# car-radar.net
KiCad netlist of a schematic drawn in Altium Designer
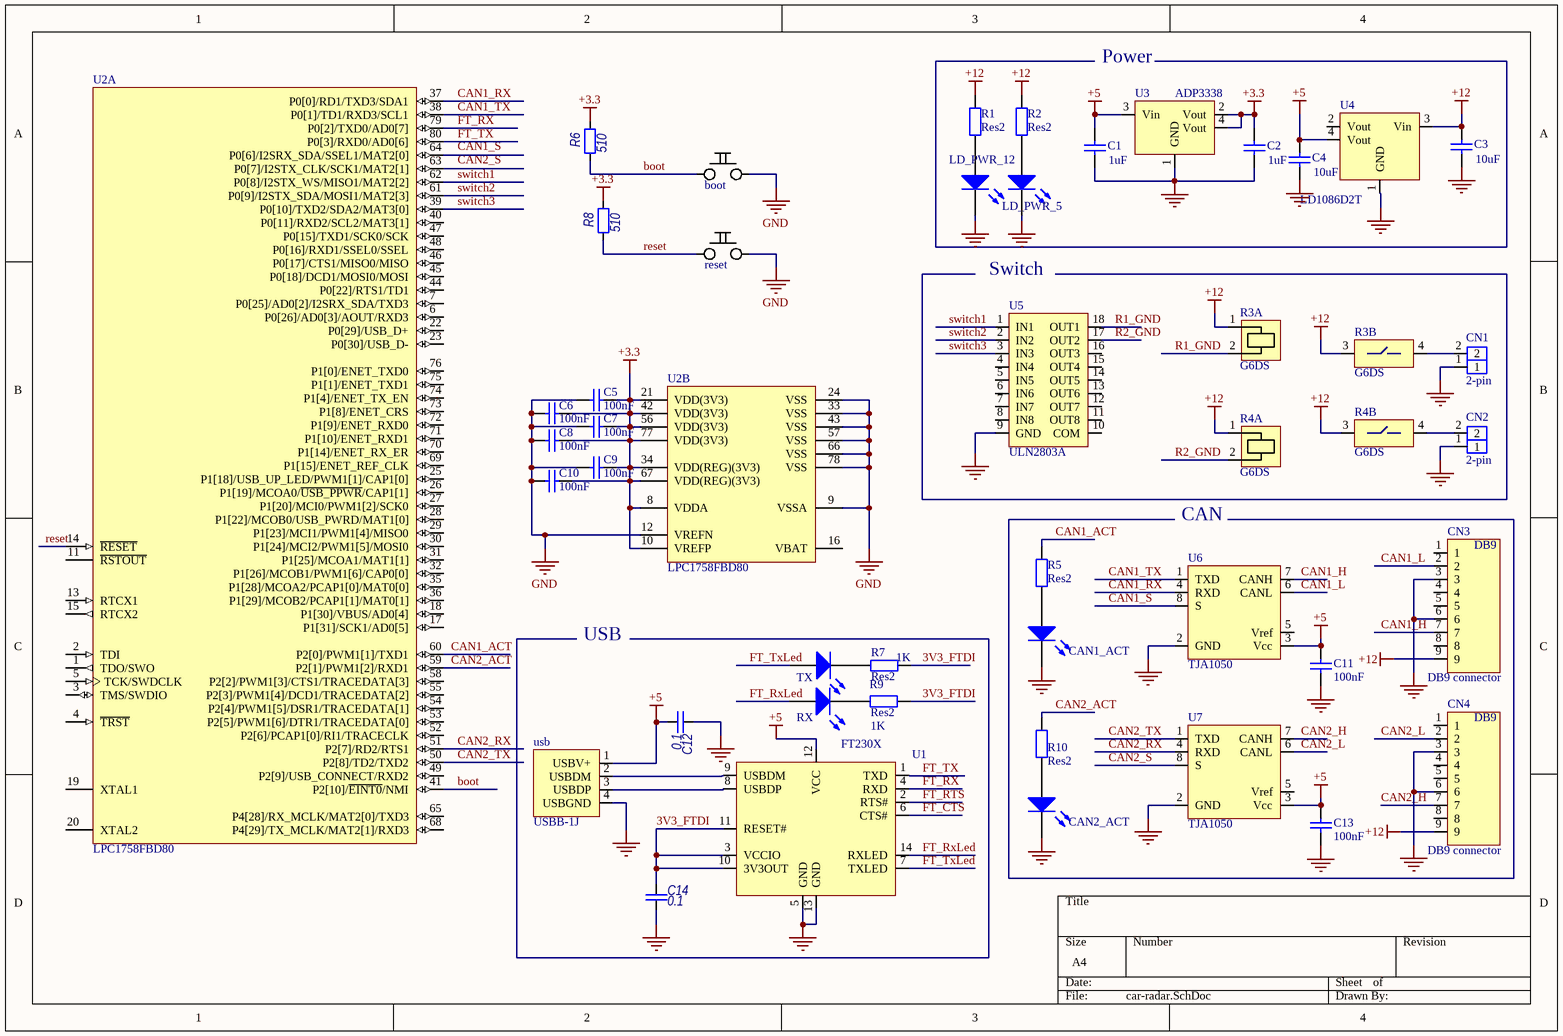
[diagram p0: car-radar.SchDoc]

(export (version "E")
  (design (tool "Eeschema 10.0.6"))
  (components
    (comp (ref "boot")
      (value "chip button")
      (footprint "BUTTON SMD")
      (libsource (lib "Schlib1") (part "chip button"))
    )
    (comp (ref "C1")
      (value "1uF")
      (footprint "CAPC1608M")
      (description "Capacitor")
      (fields (field (name "Comment") "Cap") (field (name "PUBLISHER") "Altium Limited"))
      (libsource (lib "Miscellaneous Devices") (part "Cap"))
    )
    (comp (ref "C2")
      (value "1uF")
      (footprint "CAPC1608M")
      (description "Capacitor")
      (fields (field (name "Comment") "Cap") (field (name "PUBLISHER") "Altium Limited"))
      (libsource (lib "Miscellaneous Devices") (part "Cap"))
    )
    (comp (ref "C3")
      (value "10uF")
      (footprint "CAPC1608N")
      (description "Capacitor")
      (fields (field (name "Comment") "Cap") (field (name "PUBLISHER") "Altium Limited"))
      (libsource (lib "Miscellaneous Devices") (part "Cap"))
    )
    (comp (ref "C4")
      (value "10uF")
      (footprint "CAPC1608N")
      (description "Capacitor")
      (fields (field (name "Comment") "Cap") (field (name "PUBLISHER") "Altium Limited"))
      (libsource (lib "Miscellaneous Devices") (part "Cap"))
    )
    (comp (ref "C5")
      (value "100nF")
      (footprint "CAPC1608N")
      (description "Capacitor")
      (fields (field (name "Comment") "p") (field (name "PUBLISHER") "Altium Limited"))
      (libsource (lib "Miscellaneous Devices") (part "Cap"))
    )
    (comp (ref "C6")
      (value "100nF")
      (footprint "CAPC1608N")
      (description "Capacitor")
      (fields (field (name "Comment") "p") (field (name "PUBLISHER") "Altium Limited"))
      (libsource (lib "Miscellaneous Devices") (part "Cap"))
    )
    (comp (ref "C7")
      (value "100nF")
      (footprint "CAPC1608N")
      (description "Capacitor")
      (fields (field (name "Comment") "p") (field (name "PUBLISHER") "Altium Limited"))
      (libsource (lib "Miscellaneous Devices") (part "Cap"))
    )
    (comp (ref "C8")
      (value "100nF")
      (footprint "CAPC1608N")
      (description "Capacitor")
      (fields (field (name "Comment") "p") (field (name "PUBLISHER") "Altium Limited"))
      (libsource (lib "Miscellaneous Devices") (part "Cap"))
    )
    (comp (ref "C9")
      (value "100nF")
      (footprint "CAPC1608N")
      (description "Capacitor")
      (fields (field (name "Comment") "p") (field (name "PUBLISHER") "Altium Limited"))
      (libsource (lib "Miscellaneous Devices") (part "Cap"))
    )
    (comp (ref "C10")
      (value "100nF")
      (footprint "CAPC1608N")
      (description "Capacitor")
      (fields (field (name "Comment") "p") (field (name "PUBLISHER") "Altium Limited"))
      (libsource (lib "Miscellaneous Devices") (part "Cap"))
    )
    (comp (ref "C11")
      (value "100nF")
      (footprint "CAPC1608N")
      (description "Capacitor")
      (fields (field (name "Comment") "p") (field (name "PUBLISHER") "Altium Limited"))
      (libsource (lib "Miscellaneous Devices") (part "Cap"))
    )
    (comp (ref "C12")
      (value "0.1")
      (footprint "CAPC1608M")
      (description "Ceramic capacitors")
      (libsource (lib "RCL") (part "Cap"))
    )
    (comp (ref "C13")
      (value "100nF")
      (footprint "CAPC1608N")
      (description "Capacitor")
      (fields (field (name "Comment") "p") (field (name "PUBLISHER") "Altium Limited"))
      (libsource (lib "Miscellaneous Devices") (part "Cap"))
    )
    (comp (ref "C14")
      (value "0.1")
      (footprint "Cap_0805")
      (description "Ceramic capacitors")
      (libsource (lib "RCL") (part "Cap"))
    )
    (comp (ref "CAN1_ACT")
      (value "led")
      (footprint "RESC1608M")
      (description "chip led")
      (libsource (lib "Schlib1") (part "chip led"))
    )
    (comp (ref "CAN2_ACT")
      (value "led")
      (footprint "RESC1608M")
      (description "chip led")
      (libsource (lib "Schlib1") (part "chip led"))
    )
    (comp (ref "CN1") (value "2-pin") (libsource (lib "Con sch") (part "2-pin")))
    (comp (ref "CN2") (value "2-pin") (libsource (lib "Con sch") (part "2-pin")))
    (comp (ref "CN3")
      (value "DB9 connector")
      (footprint "Con Rect Stag PCB:DSUB1.385-2H9C")
      (libsource (lib "Schlib1") (part "DB9 разъём"))
    )
    (comp (ref "CN4")
      (value "DB9 connector")
      (footprint "Con Rect Stag PCB:DSUB1.385-2H9C")
      (libsource (lib "Schlib1") (part "DB9 разъём"))
    )
    (comp (ref "LD_PWR_5")
      (value "led")
      (footprint "RESC1608M")
      (description "chip led")
      (libsource (lib "Schlib1") (part "chip led"))
    )
    (comp (ref "LD_PWR_12")
      (value "led")
      (footprint "RESC1608M")
      (description "chip led")
      (libsource (lib "Schlib1") (part "chip led"))
    )
    (comp (ref "R1")
      (value "Res2")
      (footprint "RESC3216M")
      (description "Resistor")
      (fields (field (name "PUBLISHER") "Altium Limited"))
      (libsource (lib "Miscellaneous Devices") (part "Res2"))
    )
    (comp (ref "R2")
      (value "Res2")
      (footprint "RESC3216M")
      (description "Resistor")
      (fields (field (name "PUBLISHER") "Altium Limited"))
      (libsource (lib "Miscellaneous Devices") (part "Res2"))
    )
    (comp (ref "R3")
      (value "G6DS")
      (description "SPST-NO rele")
      (libsource (lib "Schlib1") (part "rele-SPST-NO"))
    )
    (comp (ref "R4")
      (value "G6DS")
      (description "SPST-NO rele")
      (libsource (lib "Schlib1") (part "rele-SPST-NO"))
    )
    (comp (ref "R5")
      (value "Res2")
      (footprint "RESC3216M")
      (description "Resistor")
      (fields (field (name "PUBLISHER") "Altium Limited"))
      (libsource (lib "Miscellaneous Devices") (part "Res2"))
    )
    (comp (ref "R6")
      (value "510")
      (footprint "RESC2012M")
      (description "Ceramic resisors")
      (libsource (lib "RCL") (part "Res"))
    )
    (comp (ref "R7")
      (value "Res2")
      (footprint "RESC3216M")
      (description "Resistor")
      (fields (field (name "ALTIUM_VALUE") "1K") (field (name "PUBLISHER") "Altium Limited"))
      (libsource (lib "") (part "Res2_1"))
    )
    (comp (ref "R8")
      (value "510")
      (footprint "RESC2012M")
      (description "Ceramic resisors")
      (libsource (lib "RCL") (part "Res"))
    )
    (comp (ref "R9")
      (value "Res2")
      (footprint "RESC3216M")
      (description "Resistor")
      (fields (field (name "ALTIUM_VALUE") "1K") (field (name "PUBLISHER") "Altium Limited"))
      (libsource (lib "") (part "Res2_1"))
    )
    (comp (ref "R10")
      (value "Res2")
      (footprint "RESC3216M")
      (description "Resistor")
      (fields (field (name "PUBLISHER") "Altium Limited"))
      (libsource (lib "Miscellaneous Devices") (part "Res2"))
    )
    (comp (ref "reset")
      (value "chip button")
      (footprint "BUTTON SMD")
      (libsource (lib "Schlib1") (part "chip button"))
    )
    (comp (ref "RX")
      (value "led")
      (footprint "RESC2012M")
      (description "chip led")
      (libsource (lib "Schlib1") (part "chip led"))
    )
    (comp (ref "TX")
      (value "led")
      (footprint "RESC2012M")
      (description "chip led")
      (libsource (lib "Schlib1") (part "chip led"))
    )
    (comp (ref "U1")
      (value "FT230X")
      (footprint "SOP635P600-16N")
      (libsource (lib "Schlib1") (part "FT230X"))
    )
    (comp (ref "U2")
      (value "LPC1758FBD80")
      (footprint "SOT315-1_V")
      (libsource (lib "") (part "LPC1758FBD80_1"))
    )
    (comp (ref "U3")
      (value "ADP3338")
      (footprint "SOT223-4M")
      (description "ADP3339AKCZ-3.3-R7")
      (libsource (lib "Schlib1") (part "ADP3339"))
    )
    (comp (ref "U4")
      (value "LD1086D2T")
      (footprint "TO228P960-3_4M")
      (description "st LD1086D2T")
      (libsource (lib "Schlib1") (part "LD1086D2T"))
    )
    (comp (ref "U5")
      (value "ULN2803A")
      (footprint "SOIC127P1030-18L")
      (description "EIGHT DARLINGTON ARRAYS")
      (libsource (lib "Schlib1") (part "ULN2803A"))
    )
    (comp (ref "U6")
      (value "TJA1050")
      (description "High speed CAN transceiver")
      (libsource (lib "nxp") (part "TJA1050"))
    )
    (comp (ref "U7")
      (value "TJA1050")
      (description "High speed CAN transceiver")
      (libsource (lib "nxp") (part "TJA1050"))
    )
    (comp (ref "usb") (value "USBB-1J") (footprint "USB2.5-2V4") (libsource (lib "Schlib1") (part "USBB-1J")))
  )
  (nets
    (net (code "1") (name "+3.3") (class "Default")
      (node (ref "C10") (pin "2") (pinfunction "2_2") (pintype "passive"))
      (node (ref "C2") (pin "1") (pinfunction "1_1") (pintype "passive"))
      (node (ref "C5") (pin "2") (pinfunction "2_2") (pintype "passive"))
      (node (ref "C6") (pin "2") (pinfunction "2_2") (pintype "passive"))
      (node (ref "C7") (pin "2") (pinfunction "2_2") (pintype "passive"))
      (node (ref "C8") (pin "2") (pinfunction "2_2") (pintype "passive"))
      (node (ref "C9") (pin "2") (pinfunction "2_2") (pintype "passive"))
      (node (ref "R6") (pin "2") (pinfunction "2_2") (pintype "passive"))
      (node (ref "R8") (pin "2") (pinfunction "2_2") (pintype "passive"))
      (node (ref "U2") (pin "10") (pinfunction "VREFP_10") (pintype "power_in"))
      (node (ref "U2") (pin "21") (pinfunction "VDD(3V3)_21") (pintype "power_in"))
      (node (ref "U2") (pin "34") (pinfunction "VDD(REG)(3V3)_34") (pintype "power_in"))
      (node (ref "U2") (pin "42") (pinfunction "VDD(3V3)_42") (pintype "power_in"))
      (node (ref "U2") (pin "56") (pinfunction "VDD(3V3)_56") (pintype "power_in"))
      (node (ref "U2") (pin "67") (pinfunction "VDD(REG)(3V3)_67") (pintype "power_in"))
      (node (ref "U2") (pin "77") (pinfunction "VDD(3V3)_77") (pintype "power_in"))
      (node (ref "U2") (pin "8") (pinfunction "VDDA_8") (pintype "power_in"))
      (node (ref "U3") (pin "2") (pinfunction "Vout_2") (pintype "power_in"))
      (node (ref "U3") (pin "4") (pinfunction "Vout_4") (pintype "passive"))
    )
    (net (code "2") (name "+5") (class "Default")
      (node (ref "C1") (pin "1") (pinfunction "1_1") (pintype "passive"))
      (node (ref "C11") (pin "2") (pinfunction "2_2") (pintype "passive"))
      (node (ref "C12") (pin "2") (pinfunction "2_2") (pintype "passive"))
      (node (ref "C13") (pin "2") (pinfunction "2_2") (pintype "passive"))
      (node (ref "C4") (pin "1") (pinfunction "1_1") (pintype "passive"))
      (node (ref "U1") (pin "12") (pinfunction "VCC_12") (pintype "passive"))
      (node (ref "U3") (pin "3") (pinfunction "Vin_3") (pintype "power_in"))
      (node (ref "U4") (pin "4") (pinfunction "Vout_4") (pintype "passive"))
      (node (ref "U6") (pin "3") (pinfunction "Vcc_3") (pintype "passive"))
      (node (ref "U7") (pin "3") (pinfunction "Vcc_3") (pintype "passive"))
      (node (ref "usb") (pin "1") (pinfunction "USBV+_1") (pintype "power_in"))
    )
    (net (code "3") (name "+12") (class "Default")
      (node (ref "C3") (pin "1") (pinfunction "1_1") (pintype "passive"))
      (node (ref "CN3") (pin "9") (pinfunction "9_9") (pintype "passive"))
      (node (ref "CN4") (pin "9") (pinfunction "9_9") (pintype "passive"))
      (node (ref "R1") (pin "2") (pinfunction "2_2") (pintype "passive"))
      (node (ref "R2") (pin "2") (pinfunction "2_2") (pintype "passive"))
      (node (ref "R3") (pin "1") (pintype "passive"))
      (node (ref "R3") (pin "3") (pintype "passive"))
      (node (ref "R4") (pin "1") (pintype "passive"))
      (node (ref "R4") (pin "3") (pintype "passive"))
      (node (ref "U4") (pin "3") (pinfunction "Vin_3") (pintype "passive"))
    )
    (net (code "4") (name "/3V3_FTDI") (class "Default")
      (node (ref "C14") (pin "1") (pinfunction "1_1") (pintype "passive"))
      (node (ref "R7") (pin "1") (pinfunction "1_1") (pintype "passive"))
      (node (ref "R9") (pin "1") (pinfunction "1_1") (pintype "passive"))
      (node (ref "U1") (pin "10") (pinfunction "3V3OUT_10") (pintype "passive"))
      (node (ref "U1") (pin "11") (pinfunction "RESET#_11") (pintype "passive"))
      (node (ref "U1") (pin "3") (pinfunction "VCCIO_3") (pintype "passive"))
    )
    (net (code "5") (name "/CAN1_ACT") (class "Default")
      (node (ref "R5") (pin "2") (pinfunction "2_2") (pintype "passive"))
      (node (ref "U2") (pin "60") (pinfunction "P2[0]/PWM1[1]/TXD1_60") (pintype "bidirectional"))
    )
    (net (code "6") (name "/CAN1_H") (class "Default")
      (node (ref "CN3") (pin "7") (pinfunction "7_7") (pintype "passive"))
      (node (ref "U6") (pin "7") (pinfunction "CANH_7") (pintype "passive"))
    )
    (net (code "7") (name "/CAN1_L") (class "Default")
      (node (ref "CN3") (pin "2") (pinfunction "2_2") (pintype "passive"))
      (node (ref "U6") (pin "6") (pinfunction "CANL_6") (pintype "passive"))
    )
    (net (code "8") (name "/CAN1_RX") (class "Default")
      (node (ref "U2") (pin "37") (pinfunction "P0[0]/RD1/TXD3/SDA1_37") (pintype "bidirectional"))
      (node (ref "U6") (pin "4") (pinfunction "RXD_4") (pintype "passive"))
    )
    (net (code "9") (name "/CAN1_S") (class "Default")
      (node (ref "U6") (pin "8") (pinfunction "S_8") (pintype "passive"))
    )
    (net (code "10") (name "/CAN1_TX") (class "Default")
      (node (ref "U2") (pin "38") (pinfunction "P0[1]/TD1/RXD3/SCL1_38") (pintype "bidirectional"))
      (node (ref "U6") (pin "1") (pinfunction "TXD_1") (pintype "passive"))
    )
    (net (code "11") (name "/CAN2_ACT") (class "Default")
      (node (ref "R10") (pin "2") (pinfunction "2_2") (pintype "passive"))
      (node (ref "U2") (pin "59") (pinfunction "P2[1]/PWM1[2]/RXD1_59") (pintype "bidirectional"))
    )
    (net (code "12") (name "/CAN2_H") (class "Default")
      (node (ref "CN4") (pin "7") (pinfunction "7_7") (pintype "passive"))
      (node (ref "U7") (pin "7") (pinfunction "CANH_7") (pintype "passive"))
    )
    (net (code "13") (name "/CAN2_L") (class "Default")
      (node (ref "CN4") (pin "2") (pinfunction "2_2") (pintype "passive"))
      (node (ref "U7") (pin "6") (pinfunction "CANL_6") (pintype "passive"))
    )
    (net (code "14") (name "/CAN2_RX") (class "Default")
      (node (ref "U2") (pin "51") (pinfunction "P2[7]/RD2/RTS1_51") (pintype "bidirectional"))
      (node (ref "U7") (pin "4") (pinfunction "RXD_4") (pintype "passive"))
    )
    (net (code "15") (name "/CAN2_S") (class "Default")
      (node (ref "U7") (pin "8") (pinfunction "S_8") (pintype "passive"))
    )
    (net (code "16") (name "/CAN2_TX") (class "Default")
      (node (ref "U2") (pin "50") (pinfunction "P2[8]/TD2/TXD2_50") (pintype "bidirectional"))
      (node (ref "U7") (pin "1") (pinfunction "TXD_1") (pintype "passive"))
    )
    (net (code "17") (name "/FT_CTS") (class "Default")
      (node (ref "U1") (pin "6") (pinfunction "CTS#_6") (pintype "passive"))
    )
    (net (code "18") (name "/FT_RTS") (class "Default")
      (node (ref "U1") (pin "2") (pinfunction "RTS#_2") (pintype "passive"))
    )
    (net (code "19") (name "/FT_RX") (class "Default")
      (node (ref "U1") (pin "4") (pinfunction "RXD_4") (pintype "passive"))
      (node (ref "U2") (pin "79") (pinfunction "P0[2]/TXD0/AD0[7]_79") (pintype "bidirectional"))
    )
    (net (code "20") (name "/FT_RxLed") (class "Default")
      (node (ref "RX") (pin "1") (pinfunction "A_1") (pintype "passive"))
      (node (ref "U1") (pin "14") (pinfunction "RXLED_14") (pintype "passive"))
    )
    (net (code "21") (name "/FT_TX") (class "Default")
      (node (ref "U1") (pin "1") (pinfunction "TXD_1") (pintype "passive"))
      (node (ref "U2") (pin "80") (pinfunction "P0[3]/RXD0/AD0[6]_80") (pintype "bidirectional"))
    )
    (net (code "22") (name "/FT_TxLed") (class "Default")
      (node (ref "TX") (pin "1") (pinfunction "A_1") (pintype "passive"))
      (node (ref "U1") (pin "7") (pinfunction "TXLED_7") (pintype "passive"))
    )
    (net (code "23") (name "/R1_GND") (class "Default")
      (node (ref "R3") (pin "2") (pintype "passive"))
      (node (ref "U5") (pin "18") (pinfunction "OUT1_18") (pintype "passive"))
    )
    (net (code "24") (name "/R2_GND") (class "Default")
      (node (ref "R4") (pin "2") (pintype "passive"))
      (node (ref "U5") (pin "17") (pinfunction "OUT2_17") (pintype "passive"))
    )
    (net (code "25") (name "/boot") (class "Default")
      (node (ref "R6") (pin "1") (pinfunction "1_1") (pintype "passive"))
      (node (ref "U2") (pin "41") (pinfunction "P2[10]/~{EINT0}/NMI_41") (pintype "bidirectional"))
      (node (ref "boot") (pin "1") (pinfunction "1_1") (pintype "passive"))
    )
    (net (code "26") (name "/reset") (class "Default")
      (node (ref "R8") (pin "1") (pinfunction "1_1") (pintype "passive"))
      (node (ref "U2") (pin "14") (pinfunction "~{RESET}_14") (pintype "input"))
      (node (ref "reset") (pin "1") (pinfunction "1_1") (pintype "passive"))
    )
    (net (code "27") (name "/switch1") (class "Default")
      (node (ref "U2") (pin "62") (pinfunction "P0[8]/I2STX_WS/MISO1/MAT2[2]_62") (pintype "bidirectional"))
      (node (ref "U5") (pin "1") (pinfunction "IN1_1") (pintype "passive"))
    )
    (net (code "28") (name "/switch2") (class "Default")
      (node (ref "U2") (pin "61") (pinfunction "P0[9]/I2STX_SDA/MOSI1/MAT2[3]_61") (pintype "bidirectional"))
      (node (ref "U5") (pin "2") (pinfunction "IN2_2") (pintype "passive"))
    )
    (net (code "29") (name "/switch3") (class "Default")
      (node (ref "U2") (pin "39") (pinfunction "P0[10]/TXD2/SDA2/MAT3[0]_39") (pintype "bidirectional"))
      (node (ref "U5") (pin "3") (pinfunction "IN3_3") (pintype "passive"))
    )
    (net (code "30") (name "GND") (class "Default")
      (node (ref "C1") (pin "2") (pinfunction "2_2") (pintype "passive"))
      (node (ref "C10") (pin "1") (pinfunction "1_1") (pintype "passive"))
      (node (ref "C11") (pin "1") (pinfunction "1_1") (pintype "passive"))
      (node (ref "C12") (pin "1") (pinfunction "1_1") (pintype "passive"))
      (node (ref "C13") (pin "1") (pinfunction "1_1") (pintype "passive"))
      (node (ref "C14") (pin "2") (pinfunction "2_2") (pintype "passive"))
      (node (ref "C2") (pin "2") (pinfunction "2_2") (pintype "passive"))
      (node (ref "C3") (pin "2") (pinfunction "2_2") (pintype "passive"))
      (node (ref "C4") (pin "2") (pinfunction "2_2") (pintype "passive"))
      (node (ref "C5") (pin "1") (pinfunction "1_1") (pintype "passive"))
      (node (ref "C6") (pin "1") (pinfunction "1_1") (pintype "passive"))
      (node (ref "C7") (pin "1") (pinfunction "1_1") (pintype "passive"))
      (node (ref "C8") (pin "1") (pinfunction "1_1") (pintype "passive"))
      (node (ref "C9") (pin "1") (pinfunction "1_1") (pintype "passive"))
      (node (ref "CAN1_ACT") (pin "2") (pinfunction "K_2") (pintype "passive"))
      (node (ref "CAN2_ACT") (pin "2") (pinfunction "K_2") (pintype "passive"))
      (node (ref "CN1") (pin "1") (pinfunction "1_1") (pintype "passive"))
      (node (ref "CN2") (pin "1") (pinfunction "1_1") (pintype "passive"))
      (node (ref "CN3") (pin "3") (pinfunction "3_3") (pintype "passive"))
      (node (ref "CN3") (pin "6") (pinfunction "6_6") (pintype "passive"))
      (node (ref "CN4") (pin "3") (pinfunction "3_3") (pintype "passive"))
      (node (ref "CN4") (pin "6") (pinfunction "6_6") (pintype "passive"))
      (node (ref "LD_PWR_12") (pin "2") (pinfunction "K_2") (pintype "passive"))
      (node (ref "LD_PWR_5") (pin "2") (pinfunction "K_2") (pintype "passive"))
      (node (ref "U1") (pin "13") (pinfunction "GND_13") (pintype "passive"))
      (node (ref "U1") (pin "5") (pinfunction "GND_5") (pintype "passive"))
      (node (ref "U2") (pin "12") (pinfunction "VREFN_12") (pintype "power_in"))
      (node (ref "U2") (pin "24") (pinfunction "VSS_24") (pintype "power_in"))
      (node (ref "U2") (pin "33") (pinfunction "VSS_33") (pintype "power_in"))
      (node (ref "U2") (pin "43") (pinfunction "VSS_43") (pintype "power_in"))
      (node (ref "U2") (pin "57") (pinfunction "VSS_57") (pintype "power_in"))
      (node (ref "U2") (pin "66") (pinfunction "VSS_66") (pintype "power_in"))
      (node (ref "U2") (pin "78") (pinfunction "VSS_78") (pintype "power_in"))
      (node (ref "U2") (pin "9") (pinfunction "VSSA_9") (pintype "power_in"))
      (node (ref "U3") (pin "1") (pinfunction "GND_1") (pintype "power_in"))
      (node (ref "U4") (pin "1") (pinfunction "GND_1") (pintype "passive"))
      (node (ref "U5") (pin "9") (pinfunction "GND_9") (pintype "passive"))
      (node (ref "U6") (pin "2") (pinfunction "GND_2") (pintype "passive"))
      (node (ref "U7") (pin "2") (pinfunction "GND_2") (pintype "passive"))
      (node (ref "boot") (pin "2") (pinfunction "2_2") (pintype "passive"))
      (node (ref "reset") (pin "2") (pinfunction "2_2") (pintype "passive"))
      (node (ref "usb") (pin "4") (pinfunction "USBGND_4") (pintype "power_in"))
    )
    (net (code "31") (name "Net-(CAN1_ACT-A)") (class "Default")
      (node (ref "CAN1_ACT") (pin "1") (pinfunction "A_1") (pintype "passive"))
      (node (ref "R5") (pin "1") (pinfunction "1_1") (pintype "passive"))
    )
    (net (code "32") (name "Net-(CAN2_ACT-A)") (class "Default")
      (node (ref "CAN2_ACT") (pin "1") (pinfunction "A_1") (pintype "passive"))
      (node (ref "R10") (pin "1") (pinfunction "1_1") (pintype "passive"))
    )
    (net (code "33") (name "Net-(CN1-Pad2)") (class "Default")
      (node (ref "CN1") (pin "2") (pinfunction "2_2") (pintype "passive"))
      (node (ref "R3") (pin "4") (pintype "passive"))
    )
    (net (code "34") (name "Net-(CN2-Pad2)") (class "Default")
      (node (ref "CN2") (pin "2") (pinfunction "2_2") (pintype "passive"))
      (node (ref "R4") (pin "4") (pintype "passive"))
    )
    (net (code "35") (name "Net-(LD_PWR_5-A)") (class "Default")
      (node (ref "LD_PWR_5") (pin "1") (pinfunction "A_1") (pintype "passive"))
      (node (ref "R2") (pin "1") (pinfunction "1_1") (pintype "passive"))
    )
    (net (code "36") (name "Net-(LD_PWR_12-A)") (class "Default")
      (node (ref "LD_PWR_12") (pin "1") (pinfunction "A_1") (pintype "passive"))
      (node (ref "R1") (pin "1") (pinfunction "1_1") (pintype "passive"))
    )
    (net (code "37") (name "Net-(RX-K)") (class "Default")
      (node (ref "R9") (pin "2") (pinfunction "2_2") (pintype "passive"))
      (node (ref "RX") (pin "2") (pinfunction "K_2") (pintype "passive"))
    )
    (net (code "38") (name "Net-(TX-K)") (class "Default")
      (node (ref "R7") (pin "2") (pinfunction "2_2") (pintype "passive"))
      (node (ref "TX") (pin "2") (pinfunction "K_2") (pintype "passive"))
    )
    (net (code "39") (name "Net-(U1-USBDM)") (class "Default")
      (node (ref "U1") (pin "9") (pinfunction "USBDM_9") (pintype "passive"))
      (node (ref "usb") (pin "2") (pinfunction "USBDM_2") (pintype "passive"))
    )
    (net (code "40") (name "Net-(U1-USBDP)") (class "Default")
      (node (ref "U1") (pin "8") (pinfunction "USBDP_8") (pintype "passive"))
      (node (ref "usb") (pin "3") (pinfunction "USBDP_3") (pintype "passive"))
    )
    (net (code "41") (name "unconnected-(CN3-Pad1)") (class "Default")
      (node (ref "CN3") (pin "1") (pinfunction "1_1") (pintype "passive"))
    )
    (net (code "42") (name "unconnected-(CN3-Pad4)") (class "Default")
      (node (ref "CN3") (pin "4") (pinfunction "4_4") (pintype "passive"))
    )
    (net (code "43") (name "unconnected-(CN3-Pad5)") (class "Default")
      (node (ref "CN3") (pin "5") (pinfunction "5_5") (pintype "passive"))
    )
    (net (code "44") (name "unconnected-(CN3-Pad8)") (class "Default")
      (node (ref "CN3") (pin "8") (pinfunction "8_8") (pintype "passive"))
    )
    (net (code "45") (name "unconnected-(CN4-Pad1)") (class "Default")
      (node (ref "CN4") (pin "1") (pinfunction "1_1") (pintype "passive"))
    )
    (net (code "46") (name "unconnected-(CN4-Pad4)") (class "Default")
      (node (ref "CN4") (pin "4") (pinfunction "4_4") (pintype "passive"))
    )
    (net (code "47") (name "unconnected-(CN4-Pad5)") (class "Default")
      (node (ref "CN4") (pin "5") (pinfunction "5_5") (pintype "passive"))
    )
    (net (code "48") (name "unconnected-(CN4-Pad8)") (class "Default")
      (node (ref "CN4") (pin "8") (pinfunction "8_8") (pintype "passive"))
    )
    (net (code "49") (name "unconnected-(U1-CBUS0-Pad15)") (class "Default")
      (node (ref "U1") (pin "15") (pinfunction "CBUS0_15") (pintype "passive"))
    )
    (net (code "50") (name "unconnected-(U1-CBUS3-Pad16)") (class "Default")
      (node (ref "U1") (pin "16") (pinfunction "CBUS3_16") (pintype "passive"))
    )
    (net (code "51") (name "unconnected-(U2A-P0[6]{slash}I2SRX_SDA{slash}SSEL1{slash}MAT2[0]-Pad64)") (class "Default")
      (node (ref "U2") (pin "64") (pinfunction "P0[6]/I2SRX_SDA/SSEL1/MAT2[0]_64") (pintype "bidirectional"))
    )
    (net (code "52") (name "unconnected-(U2A-P0[7]{slash}I2STX_CLK{slash}SCK1{slash}MAT2[1]-Pad63)") (class "Default")
      (node (ref "U2") (pin "63") (pinfunction "P0[7]/I2STX_CLK/SCK1/MAT2[1]_63") (pintype "bidirectional"))
    )
    (net (code "53") (name "unconnected-(U2A-P0[11]{slash}RXD2{slash}SCL2{slash}MAT3[1]-Pad40)") (class "Default")
      (node (ref "U2") (pin "40") (pinfunction "P0[11]/RXD2/SCL2/MAT3[1]_40") (pintype "bidirectional"))
    )
    (net (code "54") (name "unconnected-(U2A-P0[15]{slash}TXD1{slash}SCK0{slash}SCK-Pad47)") (class "Default")
      (node (ref "U2") (pin "47") (pinfunction "P0[15]/TXD1/SCK0/SCK_47") (pintype "bidirectional"))
    )
    (net (code "55") (name "unconnected-(U2A-P0[16]{slash}RXD1{slash}SSEL0{slash}SSEL-Pad48)") (class "Default")
      (node (ref "U2") (pin "48") (pinfunction "P0[16]/RXD1/SSEL0/SSEL_48") (pintype "bidirectional"))
    )
    (net (code "56") (name "unconnected-(U2A-P0[17]{slash}CTS1{slash}MISO0{slash}MISO-Pad46)") (class "Default")
      (node (ref "U2") (pin "46") (pinfunction "P0[17]/CTS1/MISO0/MISO_46") (pintype "bidirectional"))
    )
    (net (code "57") (name "unconnected-(U2A-P0[18]{slash}DCD1{slash}MOSI0{slash}MOSI-Pad45)") (class "Default")
      (node (ref "U2") (pin "45") (pinfunction "P0[18]/DCD1/MOSI0/MOSI_45") (pintype "bidirectional"))
    )
    (net (code "58") (name "unconnected-(U2A-P0[22]{slash}RTS1{slash}TD1-Pad44)") (class "Default")
      (node (ref "U2") (pin "44") (pinfunction "P0[22]/RTS1/TD1_44") (pintype "bidirectional"))
    )
    (net (code "59") (name "unconnected-(U2A-P0[25]{slash}AD0[2]{slash}I2SRX_SDA{slash}TXD3-Pad7)") (class "Default")
      (node (ref "U2") (pin "7") (pinfunction "P0[25]/AD0[2]/I2SRX_SDA/TXD3_7") (pintype "bidirectional"))
    )
    (net (code "60") (name "unconnected-(U2A-P0[26]{slash}AD0[3]{slash}AOUT{slash}RXD3-Pad6)") (class "Default")
      (node (ref "U2") (pin "6") (pinfunction "P0[26]/AD0[3]/AOUT/RXD3_6") (pintype "bidirectional"))
    )
    (net (code "61") (name "unconnected-(U2A-P0[29]{slash}USB_D+-Pad22)") (class "Default")
      (node (ref "U2") (pin "22") (pinfunction "P0[29]/USB_D+_22") (pintype "bidirectional"))
    )
    (net (code "62") (name "unconnected-(U2A-P0[30]{slash}USB_D--Pad23)") (class "Default")
      (node (ref "U2") (pin "23") (pinfunction "P0[30]/USB_D-_23") (pintype "bidirectional"))
    )
    (net (code "63") (name "unconnected-(U2A-P1[0]{slash}ENET_TXD0-Pad76)") (class "Default")
      (node (ref "U2") (pin "76") (pinfunction "P1[0]/ENET_TXD0_76") (pintype "bidirectional"))
    )
    (net (code "64") (name "unconnected-(U2A-P1[1]{slash}ENET_TXD1-Pad75)") (class "Default")
      (node (ref "U2") (pin "75") (pinfunction "P1[1]/ENET_TXD1_75") (pintype "bidirectional"))
    )
    (net (code "65") (name "unconnected-(U2A-P1[4]{slash}ENET_TX_EN-Pad74)") (class "Default")
      (node (ref "U2") (pin "74") (pinfunction "P1[4]/ENET_TX_EN_74") (pintype "bidirectional"))
    )
    (net (code "66") (name "unconnected-(U2A-P1[8]{slash}ENET_CRS-Pad73)") (class "Default")
      (node (ref "U2") (pin "73") (pinfunction "P1[8]/ENET_CRS_73") (pintype "bidirectional"))
    )
    (net (code "67") (name "unconnected-(U2A-P1[9]{slash}ENET_RXD0-Pad72)") (class "Default")
      (node (ref "U2") (pin "72") (pinfunction "P1[9]/ENET_RXD0_72") (pintype "bidirectional"))
    )
    (net (code "68") (name "unconnected-(U2A-P1[10]{slash}ENET_RXD1-Pad71)") (class "Default")
      (node (ref "U2") (pin "71") (pinfunction "P1[10]/ENET_RXD1_71") (pintype "bidirectional"))
    )
    (net (code "69") (name "unconnected-(U2A-P1[14]{slash}ENET_RX_ER-Pad70)") (class "Default")
      (node (ref "U2") (pin "70") (pinfunction "P1[14]/ENET_RX_ER_70") (pintype "bidirectional"))
    )
    (net (code "70") (name "unconnected-(U2A-P1[15]{slash}ENET_REF_CLK-Pad69)") (class "Default")
      (node (ref "U2") (pin "69") (pinfunction "P1[15]/ENET_REF_CLK_69") (pintype "bidirectional"))
    )
    (net (code "71") (name "unconnected-(U2A-P1[18]{slash}USB_UP_LED{slash}PWM1[1]{slash}CAP1[0]-Pad25)") (class "Default")
      (node (ref "U2") (pin "25") (pinfunction "P1[18]/USB_UP_LED/PWM1[1]/CAP1[0]_25") (pintype "bidirectional"))
    )
    (net (code "72") (name "unconnected-(U2A-P1[19]{slash}MCOA0{slash}~{USB_PPWR}{slash}CAP1[1]-Pad26)") (class "Default")
      (node (ref "U2") (pin "26") (pinfunction "P1[19]/MCOA0/~{USB_PPWR}/CAP1[1]_26") (pintype "bidirectional"))
    )
    (net (code "73") (name "unconnected-(U2A-P1[20]{slash}MCI0{slash}PWM1[2]{slash}SCK0-Pad27)") (class "Default")
      (node (ref "U2") (pin "27") (pinfunction "P1[20]/MCI0/PWM1[2]/SCK0_27") (pintype "bidirectional"))
    )
    (net (code "74") (name "unconnected-(U2A-P1[22]{slash}MCOB0{slash}USB_PWRD{slash}MAT1[0]-Pad28)") (class "Default")
      (node (ref "U2") (pin "28") (pinfunction "P1[22]/MCOB0/USB_PWRD/MAT1[0]_28") (pintype "bidirectional"))
    )
    (net (code "75") (name "unconnected-(U2A-P1[23]{slash}MCI1{slash}PWM1[4]{slash}MISO0-Pad29)") (class "Default")
      (node (ref "U2") (pin "29") (pinfunction "P1[23]/MCI1/PWM1[4]/MISO0_29") (pintype "bidirectional"))
    )
    (net (code "76") (name "unconnected-(U2A-P1[24]{slash}MCI2{slash}PWM1[5]{slash}MOSI0-Pad30)") (class "Default")
      (node (ref "U2") (pin "30") (pinfunction "P1[24]/MCI2/PWM1[5]/MOSI0_30") (pintype "bidirectional"))
    )
    (net (code "77") (name "unconnected-(U2A-P1[25]{slash}MCOA1{slash}MAT1[1]-Pad31)") (class "Default")
      (node (ref "U2") (pin "31") (pinfunction "P1[25]/MCOA1/MAT1[1]_31") (pintype "bidirectional"))
    )
    (net (code "78") (name "unconnected-(U2A-P1[26]{slash}MCOB1{slash}PWM1[6]{slash}CAP0[0]-Pad32)") (class "Default")
      (node (ref "U2") (pin "32") (pinfunction "P1[26]/MCOB1/PWM1[6]/CAP0[0]_32") (pintype "bidirectional"))
    )
    (net (code "79") (name "unconnected-(U2A-P1[28]{slash}MCOA2{slash}PCAP1[0]{slash}MAT0[0]-Pad35)") (class "Default")
      (node (ref "U2") (pin "35") (pinfunction "P1[28]/MCOA2/PCAP1[0]/MAT0[0]_35") (pintype "bidirectional"))
    )
    (net (code "80") (name "unconnected-(U2A-P1[29]{slash}MCOB2{slash}PCAP1[1]{slash}MAT0[1]-Pad36)") (class "Default")
      (node (ref "U2") (pin "36") (pinfunction "P1[29]/MCOB2/PCAP1[1]/MAT0[1]_36") (pintype "bidirectional"))
    )
    (net (code "81") (name "unconnected-(U2A-P1[30]{slash}VBUS{slash}AD0[4]-Pad18)") (class "Default")
      (node (ref "U2") (pin "18") (pinfunction "P1[30]/VBUS/AD0[4]_18") (pintype "bidirectional"))
    )
    (net (code "82") (name "unconnected-(U2A-P1[31]{slash}SCK1{slash}AD0[5]-Pad17)") (class "Default")
      (node (ref "U2") (pin "17") (pinfunction "P1[31]/SCK1/AD0[5]_17") (pintype "bidirectional"))
    )
    (net (code "83") (name "unconnected-(U2A-P2[2]{slash}PWM1[3]{slash}CTS1{slash}TRACEDATA[3]-Pad58)") (class "Default")
      (node (ref "U2") (pin "58") (pinfunction "P2[2]/PWM1[3]/CTS1/TRACEDATA[3]_58") (pintype "bidirectional"))
    )
    (net (code "84") (name "unconnected-(U2A-P2[3]{slash}PWM1[4]{slash}DCD1{slash}TRACEDATA[2]-Pad55)") (class "Default")
      (node (ref "U2") (pin "55") (pinfunction "P2[3]/PWM1[4]/DCD1/TRACEDATA[2]_55") (pintype "bidirectional"))
    )
    (net (code "85") (name "unconnected-(U2A-P2[4]{slash}PWM1[5]{slash}DSR1{slash}TRACEDATA[1]-Pad54)") (class "Default")
      (node (ref "U2") (pin "54") (pinfunction "P2[4]/PWM1[5]/DSR1/TRACEDATA[1]_54") (pintype "bidirectional"))
    )
    (net (code "86") (name "unconnected-(U2A-P2[5]{slash}PWM1[6]{slash}DTR1{slash}TRACEDATA[0]-Pad53)") (class "Default")
      (node (ref "U2") (pin "53") (pinfunction "P2[5]/PWM1[6]/DTR1/TRACEDATA[0]_53") (pintype "bidirectional"))
    )
    (net (code "87") (name "unconnected-(U2A-P2[6]{slash}PCAP1[0]{slash}RI1{slash}TRACECLK-Pad52)") (class "Default")
      (node (ref "U2") (pin "52") (pinfunction "P2[6]/PCAP1[0]/RI1/TRACECLK_52") (pintype "bidirectional"))
    )
    (net (code "88") (name "unconnected-(U2A-P2[9]{slash}USB_CONNECT{slash}RXD2-Pad49)") (class "Default")
      (node (ref "U2") (pin "49") (pinfunction "P2[9]/USB_CONNECT/RXD2_49") (pintype "bidirectional"))
    )
    (net (code "89") (name "unconnected-(U2A-P4[28]{slash}RX_MCLK{slash}MAT2[0]{slash}TXD3-Pad65)") (class "Default")
      (node (ref "U2") (pin "65") (pinfunction "P4[28]/RX_MCLK/MAT2[0]/TXD3_65") (pintype "bidirectional"))
    )
    (net (code "90") (name "unconnected-(U2A-P4[29]{slash}TX_MCLK{slash}MAT2[1]{slash}RXD3-Pad68)") (class "Default")
      (node (ref "U2") (pin "68") (pinfunction "P4[29]/TX_MCLK/MAT2[1]/RXD3_68") (pintype "bidirectional"))
    )
    (net (code "91") (name "unconnected-(U2A-RTCX1-Pad13)") (class "Default")
      (node (ref "U2") (pin "13") (pinfunction "RTCX1_13") (pintype "input"))
    )
    (net (code "92") (name "unconnected-(U2A-RTCX2-Pad15)") (class "Default")
      (node (ref "U2") (pin "15") (pinfunction "RTCX2_15") (pintype "output"))
    )
    (net (code "93") (name "unconnected-(U2A-TCK{slash}SWDCLK-Pad5)") (class "Default")
      (node (ref "U2") (pin "5") (pinfunction "TCK/SWDCLK_5") (pintype "input"))
    )
    (net (code "94") (name "unconnected-(U2A-TDI-Pad2)") (class "Default")
      (node (ref "U2") (pin "2") (pinfunction "TDI_2") (pintype "input"))
    )
    (net (code "95") (name "unconnected-(U2A-TDO{slash}SWO-Pad1)") (class "Default")
      (node (ref "U2") (pin "1") (pinfunction "TDO/SWO_1") (pintype "output"))
    )
    (net (code "96") (name "unconnected-(U2A-TMS{slash}SWDIO-Pad3)") (class "Default")
      (node (ref "U2") (pin "3") (pinfunction "TMS/SWDIO_3") (pintype "bidirectional"))
    )
    (net (code "97") (name "unconnected-(U2A-XTAL1-Pad19)") (class "Default")
      (node (ref "U2") (pin "19") (pinfunction "XTAL1_19") (pintype "passive"))
    )
    (net (code "98") (name "unconnected-(U2A-XTAL2-Pad20)") (class "Default")
      (node (ref "U2") (pin "20") (pinfunction "XTAL2_20") (pintype "passive"))
    )
    (net (code "99") (name "unconnected-(U2A-~{RSTOUT}-Pad11)") (class "Default")
      (node (ref "U2") (pin "11") (pinfunction "~{RSTOUT}_11") (pintype "passive"))
    )
    (net (code "100") (name "unconnected-(U2A-~{TRST}-Pad4)") (class "Default")
      (node (ref "U2") (pin "4") (pinfunction "~{TRST}_4") (pintype "input"))
    )
    (net (code "101") (name "unconnected-(U2B-VBAT-Pad16)") (class "Default")
      (node (ref "U2") (pin "16") (pinfunction "VBAT_16") (pintype "power_in"))
    )
    (net (code "102") (name "unconnected-(U4-Vout-Pad2)") (class "Default")
      (node (ref "U4") (pin "2") (pinfunction "Vout_2") (pintype "passive"))
    )
    (net (code "103") (name "unconnected-(U5-COM-Pad10)") (class "Default")
      (node (ref "U5") (pin "10") (pinfunction "COM_10") (pintype "passive"))
    )
    (net (code "104") (name "unconnected-(U5-IN4-Pad4)") (class "Default")
      (node (ref "U5") (pin "4") (pinfunction "IN4_4") (pintype "passive"))
    )
    (net (code "105") (name "unconnected-(U5-IN5-Pad5)") (class "Default")
      (node (ref "U5") (pin "5") (pinfunction "IN5_5") (pintype "passive"))
    )
    (net (code "106") (name "unconnected-(U5-IN6-Pad6)") (class "Default")
      (node (ref "U5") (pin "6") (pinfunction "IN6_6") (pintype "passive"))
    )
    (net (code "107") (name "unconnected-(U5-IN7-Pad7)") (class "Default")
      (node (ref "U5") (pin "7") (pinfunction "IN7_7") (pintype "passive"))
    )
    (net (code "108") (name "unconnected-(U5-IN8-Pad8)") (class "Default")
      (node (ref "U5") (pin "8") (pinfunction "IN8_8") (pintype "passive"))
    )
    (net (code "109") (name "unconnected-(U5-OUT3-Pad16)") (class "Default")
      (node (ref "U5") (pin "16") (pinfunction "OUT3_16") (pintype "passive"))
    )
    (net (code "110") (name "unconnected-(U5-OUT4-Pad15)") (class "Default")
      (node (ref "U5") (pin "15") (pinfunction "OUT4_15") (pintype "passive"))
    )
    (net (code "111") (name "unconnected-(U5-OUT5-Pad14)") (class "Default")
      (node (ref "U5") (pin "14") (pinfunction "OUT5_14") (pintype "passive"))
    )
    (net (code "112") (name "unconnected-(U5-OUT6-Pad13)") (class "Default")
      (node (ref "U5") (pin "13") (pinfunction "OUT6_13") (pintype "passive"))
    )
    (net (code "113") (name "unconnected-(U5-OUT7-Pad12)") (class "Default")
      (node (ref "U5") (pin "12") (pinfunction "OUT7_12") (pintype "passive"))
    )
    (net (code "114") (name "unconnected-(U5-OUT8-Pad11)") (class "Default")
      (node (ref "U5") (pin "11") (pinfunction "OUT8_11") (pintype "passive"))
    )
    (net (code "115") (name "unconnected-(U6-Vref-Pad5)") (class "Default")
      (node (ref "U6") (pin "5") (pinfunction "Vref_5") (pintype "passive"))
    )
    (net (code "116") (name "unconnected-(U7-Vref-Pad5)") (class "Default")
      (node (ref "U7") (pin "5") (pinfunction "Vref_5") (pintype "passive"))
    )
  )
)
